# IN_BUF.net
KiCad netlist of a schematic drawn in Altium Designer
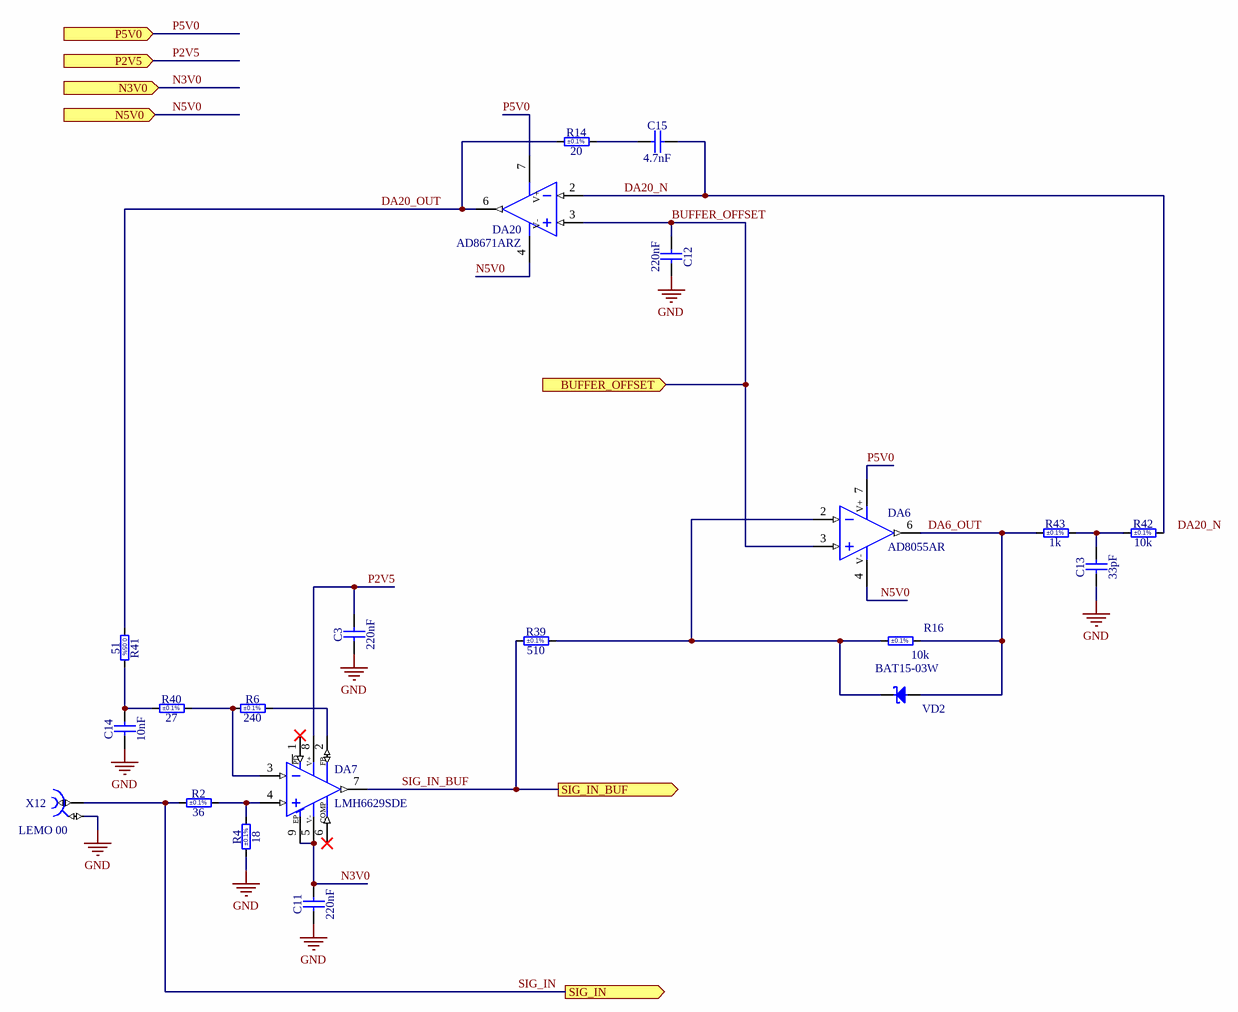
[diagram p0: IN_BUF.SchDoc]

(export (version "E")
  (design (tool "Eeschema 10.0.6"))
  (components
    (comp (ref "C3")
      (value "220nF")
      (footprint "CAPC2012X135N")
      (description "Non-polarised capacitor")
      (fields
        (field (name "PART NUMBER") "CC0805_220NF_50V_10%_X7R")
        (field (name "VOLTAGE") "50V")
        (field (name "AUTHOR") "CERN DEM JLC")
      )
      (libsource (lib "Capacitors") (part "Capacitor - non polarized"))
    )
    (comp (ref "C11")
      (value "220nF")
      (footprint "CAPC2012X135N")
      (description "Non-polarised capacitor")
      (fields
        (field (name "PART NUMBER") "CC0805_220NF_50V_10%_X7R")
        (field (name "VOLTAGE") "50V")
        (field (name "AUTHOR") "CERN DEM JLC")
      )
      (libsource (lib "Capacitors") (part "Capacitor - non polarized"))
    )
    (comp (ref "C12")
      (value "220nF")
      (footprint "CAPC2012X135N")
      (description "Non-polarised capacitor")
      (fields
        (field (name "PART NUMBER") "CC0805_220NF_50V_10%_X7R")
        (field (name "VOLTAGE") "50V")
        (field (name "AUTHOR") "CERN DEM JLC")
      )
      (libsource (lib "Capacitors") (part "Capacitor - non polarized"))
    )
    (comp (ref "C13")
      (value "33pF")
      (footprint "CAPC2013X115N")
      (description "Non-polarised capacitor")
      (fields
        (field (name "PART NUMBER") "CC0805_33PF_200V_1%_NP0")
        (field (name "VOLTAGE") "200V")
        (field (name "AUTHOR") "CERN DEM HF")
      )
      (libsource (lib "Capacitors") (part "Capacitor - non polarized"))
    )
    (comp (ref "C14")
      (value "10nF")
      (footprint "CAPC2012X135N")
      (description "Non-polarised capacitor")
      (fields
        (field (name "PART NUMBER") "CC0805_10NF_50V_2%_C0G")
        (field (name "VOLTAGE") "50V")
        (field (name "AUTHOR") "CERN DEM HF")
      )
      (libsource (lib "Capacitors") (part "Capacitor - non polarized"))
    )
    (comp (ref "C15")
      (value "4.7nF")
      (footprint "CAPC2012X135N")
      (description "Non-polarised capacitor")
      (fields
        (field (name "PART NUMBER") "CC0805_4.7NF_250V_1%_NP0")
        (field (name "VOLTAGE") "250V")
        (field (name "AUTHOR") "CERN DEM HF")
      )
      (libsource (lib "Capacitors") (part "Capacitor - non polarized"))
    )
    (comp (ref "DA6")
      (value "AD8055AR")
      (footprint "SOIC127P600X175-8N")
      (description "Operational Amplifier")
      (fields (field (name "MANUFACTURER") "ANALOG DEVICES") (field (name "AUTHOR") "CERN DEM HF"))
      (libsource (lib "ICs And Semiconductors") (part "Operational Amplifier Type1"))
    )
    (comp (ref "DA7")
      (value "LMH6629SDE")
      (footprint "TEXAS_NGQ0008A")
      (description "Ultra-Low Noise, High-Speed Operational Amplifier with Shutdown")
      (fields (field (name "MANUFACTURER") "TEXAS INSTRUMENTS") (field (name "AUTHOR") "CERN DEM HF"))
      (libsource (lib "ICs And Semiconductors") (part "LMH6629SDE"))
    )
    (comp (ref "DA20")
      (value "AD8671ARZ")
      (footprint "SOIC127P600X175-8N")
      (description "Operational Amplifier")
      (fields
        (field (name "MANUFACTURER") "ANALOG DEVICES")
        (field (name "MANUFACTURER PART NUMBER") "AD8671AR")
        (field (name "AUTHOR") "CERN DEM JLC")
      )
      (libsource (lib "ICs And Semiconductors") (part "Operational Amplifier Type1"))
    )
    (comp (ref "R2")
      (value "36")
      (footprint "RESC1608X64N")
      (description "Resistor - 0.1%")
      (fields
        (field (name "TOLERANCE") "±0.1%")
        (field (name "PART NUMBER") "R0603_36R_0.1%_0.1W_10PPM")
        (field (name "POWER") "0.1W")
        (field (name "AUTHOR") "CERN DEM HF")
      )
      (libsource (lib "Resistors") (part "Resistor - 0.1%"))
    )
    (comp (ref "R4")
      (value "18")
      (footprint "RESC1608X64N")
      (description "Resistor - 0.1%")
      (fields
        (field (name "TOLERANCE") "±0.1%")
        (field (name "PART NUMBER") "R0603_18R_0.1%_0.1W_25PPM")
        (field (name "POWER") "0.1W")
        (field (name "AUTHOR") "CERN DEM HF")
      )
      (libsource (lib "Resistors") (part "Resistor - 0.1%"))
    )
    (comp (ref "R6")
      (value "240")
      (footprint "RESC1005X40N")
      (description "Resistor - 0.1%")
      (fields
        (field (name "TOLERANCE") "±0.1%")
        (field (name "PART NUMBER") "R0402_240R_0.1%_0.0625W_10PPM")
        (field (name "POWER") "0.063W")
        (field (name "AUTHOR") "CERN DEM HF")
      )
      (libsource (lib "Resistors") (part "Resistor - 0.1%"))
    )
    (comp (ref "R14")
      (value "20")
      (footprint "RESC2012X60N")
      (description "Resistor - 0.1%")
      (fields
        (field (name "TOLERANCE") "±0.1%")
        (field (name "PART NUMBER") "R0805_20R_0.1%_0.1W_10PPM")
        (field (name "POWER") "0.1W")
        (field (name "AUTHOR") "CERN DEM JLC")
      )
      (libsource (lib "Resistors") (part "Resistor - 0.1%"))
    )
    (comp (ref "R16")
      (value "10k")
      (footprint "RESC2012X60N")
      (description "Resistor - 0.1%")
      (fields
        (field (name "TOLERANCE") "±0.1%")
        (field (name "PART NUMBER") "R0805_10K_0.1%_0.1W_10PPM")
        (field (name "POWER") "0.1W")
        (field (name "AUTHOR") "CERN DEM JLC")
      )
      (libsource (lib "Resistors") (part "Resistor - 0.1%"))
    )
    (comp (ref "R39")
      (value "510")
      (footprint "RESC1005X40N")
      (description "Resistor - 0.1%")
      (fields
        (field (name "TOLERANCE") "±0.1%")
        (field (name "PART NUMBER") "R0402_510R_0.1%_0.0625W_10PPM")
        (field (name "POWER") "0.063W")
        (field (name "AUTHOR") "CERN DEM HF")
      )
      (libsource (lib "Resistors") (part "Resistor - 0.1%"))
    )
    (comp (ref "R40")
      (value "27")
      (footprint "RESC1608X64N")
      (description "Resistor - 0.1%")
      (fields
        (field (name "TOLERANCE") "±0.1%")
        (field (name "PART NUMBER") "R0603_27R_0.1%_0.1W_10PPM")
        (field (name "POWER") "0.1W")
        (field (name "AUTHOR") "CERN DEM HF")
      )
      (libsource (lib "Resistors") (part "Resistor - 0.1%"))
    )
    (comp (ref "R41")
      (value "51")
      (footprint "RESC2012X60N")
      (description "Resistor - 0.05%")
      (fields
        (field (name "PART NUMBER") "R0805_51R_0.05%_0.125W_10PPM")
        (field (name "POWER") "0.1W")
        (field (name "AUTHOR") "CERN DEM HF")
      )
      (libsource (lib "Resistors") (part "Resistor - 0.05%"))
    )
    (comp (ref "R42")
      (value "10k")
      (footprint "RESC2012X60N")
      (description "Resistor - 0.1%")
      (fields
        (field (name "TOLERANCE") "±0.1%")
        (field (name "PART NUMBER") "R0805_10K_0.1%_0.1W_10PPM")
        (field (name "POWER") "0.1W")
        (field (name "AUTHOR") "CERN DEM JLC")
      )
      (libsource (lib "Resistors") (part "Resistor - 0.1%"))
    )
    (comp (ref "R43")
      (value "1k")
      (footprint "RESC2012X60N")
      (description "Resistor - 0.1%")
      (fields
        (field (name "TOLERANCE") "±0.1%")
        (field (name "PART NUMBER") "R0805_1K_0.1%_0.1W_10PPM")
        (field (name "POWER") "0.1W")
        (field (name "AUTHOR") "CERN DEM JLC")
      )
      (libsource (lib "Resistors") (part "Resistor - 0.1%"))
    )
    (comp (ref "VD2")
      (value "BAT15-03W")
      (footprint "SOD2512X110N")
      (description "Schottky Diode")
      (fields
        (field (name "VOLTAGE") "4V")
        (field (name "POWER") "100mA")
        (field (name "AUTHOR") "CERN DEM HF")
      )
      (libsource (lib "ICs And Semiconductors") (part "Diode Schottky"))
    )
    (comp (ref "X12")
      (value "LEMO 00")
      (footprint "LEMO_EPL.00.250.NTN")
      (fields
        (field (name "PART NUMBER") "LEMO_EPL.00.250.NTN")
        (field (name "MANUFACTURER") "LEMO")
        (field (name "MANUFACTURER PART NUMBER") "EPL.00.250.NTN")
        (field (name "AUTHOR") "CERN DEM JLC")
      )
      (libsource (lib "Connectors") (part "Coax_1Female_1Shield"))
    )
  )
  (nets
    (net (code "1") (name "/BUFFER_OFFSET") (class "Default")
      (node (ref "C12") (pin "2") (pinfunction "2_2") (pintype "passive"))
      (node (ref "DA20") (pin "3") (pinfunction "IN+_3") (pintype "input"))
      (node (ref "DA6") (pin "3") (pinfunction "IN+_3") (pintype "input"))
    )
    (net (code "2") (name "/DA6_OUT") (class "Default")
      (node (ref "DA6") (pin "6") (pinfunction "OUT_6") (pintype "output"))
      (node (ref "R16") (pin "1") (pinfunction "1_1") (pintype "passive"))
      (node (ref "R43") (pin "1") (pinfunction "1_1") (pintype "passive"))
      (node (ref "VD2") (pin "2") (pinfunction "A_2") (pintype "passive"))
    )
    (net (code "3") (name "/DA20_N") (class "Default")
      (node (ref "C15") (pin "1") (pinfunction "1_1") (pintype "passive"))
      (node (ref "DA20") (pin "2") (pinfunction "IN-_2") (pintype "input"))
      (node (ref "R42") (pin "2") (pinfunction "2_2") (pintype "passive"))
    )
    (net (code "4") (name "/DA20_OUT") (class "Default")
      (node (ref "DA20") (pin "6") (pinfunction "OUT_6") (pintype "output"))
      (node (ref "R14") (pin "2") (pinfunction "2_2") (pintype "passive"))
      (node (ref "R41") (pin "1") (pinfunction "1_1") (pintype "passive"))
    )
    (net (code "5") (name "/N3V0") (class "Default")
      (node (ref "C11") (pin "2") (pinfunction "2_2") (pintype "passive"))
      (node (ref "DA7") (pin "5") (pinfunction "V-_5") (pintype "power_in"))
      (node (ref "DA7") (pin "9") (pinfunction "EP_9") (pintype "power_in"))
    )
    (net (code "6") (name "/N5V0") (class "Default")
      (node (ref "DA20") (pin "4") (pinfunction "V-_4") (pintype "power_in"))
      (node (ref "DA6") (pin "4") (pinfunction "V-_4") (pintype "power_in"))
    )
    (net (code "7") (name "/P2V5") (class "Default")
      (node (ref "C3") (pin "2") (pinfunction "2_2") (pintype "passive"))
      (node (ref "DA7") (pin "8") (pinfunction "V+_8") (pintype "power_in"))
    )
    (net (code "8") (name "/P5V0") (class "Default")
      (node (ref "DA20") (pin "7") (pinfunction "V+_7") (pintype "power_in"))
      (node (ref "DA6") (pin "7") (pinfunction "V+_7") (pintype "power_in"))
    )
    (net (code "9") (name "/SIG_IN") (class "Default")
      (node (ref "R2") (pin "1") (pinfunction "1_1") (pintype "passive"))
      (node (ref "X12") (pin "1") (pinfunction "1_1") (pintype "bidirectional"))
    )
    (net (code "10") (name "/SIG_IN_BUF") (class "Default")
      (node (ref "DA7") (pin "7") (pinfunction "OUT_7") (pintype "output"))
      (node (ref "R39") (pin "1") (pinfunction "1_1") (pintype "passive"))
    )
    (net (code "11") (name "GND") (class "Default")
      (node (ref "C11") (pin "1") (pinfunction "1_1") (pintype "passive"))
      (node (ref "C12") (pin "1") (pinfunction "1_1") (pintype "passive"))
      (node (ref "C13") (pin "1") (pinfunction "1_1") (pintype "passive"))
      (node (ref "C14") (pin "1") (pinfunction "1_1") (pintype "passive"))
      (node (ref "C3") (pin "1") (pinfunction "1_1") (pintype "passive"))
      (node (ref "R4") (pin "1") (pinfunction "1_1") (pintype "passive"))
      (node (ref "X12") (pin "2") (pinfunction "2_2") (pintype "bidirectional"))
    )
    (net (code "12") (name "Net-(C13-Pad2)") (class "Default")
      (node (ref "C13") (pin "2") (pinfunction "2_2") (pintype "passive"))
      (node (ref "R42") (pin "1") (pinfunction "1_1") (pintype "passive"))
      (node (ref "R43") (pin "2") (pinfunction "2_2") (pintype "passive"))
    )
    (net (code "13") (name "Net-(C14-Pad2)") (class "Default")
      (node (ref "C14") (pin "2") (pinfunction "2_2") (pintype "passive"))
      (node (ref "R40") (pin "1") (pinfunction "1_1") (pintype "passive"))
      (node (ref "R41") (pin "2") (pinfunction "2_2") (pintype "passive"))
    )
    (net (code "14") (name "Net-(C15-Pad2)") (class "Default")
      (node (ref "C15") (pin "2") (pinfunction "2_2") (pintype "passive"))
      (node (ref "R14") (pin "1") (pinfunction "1_1") (pintype "passive"))
    )
    (net (code "15") (name "Net-(DA6-IN-)") (class "Default")
      (node (ref "DA6") (pin "2") (pinfunction "IN-_2") (pintype "input"))
      (node (ref "R16") (pin "2") (pinfunction "2_2") (pintype "passive"))
      (node (ref "R39") (pin "2") (pinfunction "2_2") (pintype "passive"))
      (node (ref "VD2") (pin "1") (pinfunction "C_1") (pintype "passive"))
    )
    (net (code "16") (name "Net-(DA7-FB)") (class "Default")
      (node (ref "DA7") (pin "2") (pinfunction "FB_2") (pintype "bidirectional"))
      (node (ref "R6") (pin "2") (pinfunction "2_2") (pintype "passive"))
    )
    (net (code "17") (name "Net-(DA7-IN+)") (class "Default")
      (node (ref "DA7") (pin "4") (pinfunction "IN+_4") (pintype "input"))
      (node (ref "R2") (pin "2") (pinfunction "2_2") (pintype "passive"))
      (node (ref "R4") (pin "2") (pinfunction "2_2") (pintype "passive"))
    )
    (net (code "18") (name "Net-(DA7-IN-)") (class "Default")
      (node (ref "DA7") (pin "3") (pinfunction "IN-_3") (pintype "input"))
      (node (ref "R40") (pin "2") (pinfunction "2_2") (pintype "passive"))
      (node (ref "R6") (pin "1") (pinfunction "1_1") (pintype "passive"))
    )
    (net (code "19") (name "unconnected-(DA7-COMP-Pad6)") (class "Default")
      (node (ref "DA7") (pin "6") (pinfunction "COMP_6") (pintype "input+no_connect"))
    )
    (net (code "20") (name "unconnected-(DA7-~{PD}-Pad1)") (class "Default")
      (node (ref "DA7") (pin "1") (pinfunction "~{PD}_1") (pintype "input+no_connect"))
    )
  )
)
